# rc1180.net
KiCad netlist of a schematic drawn in EAGLE
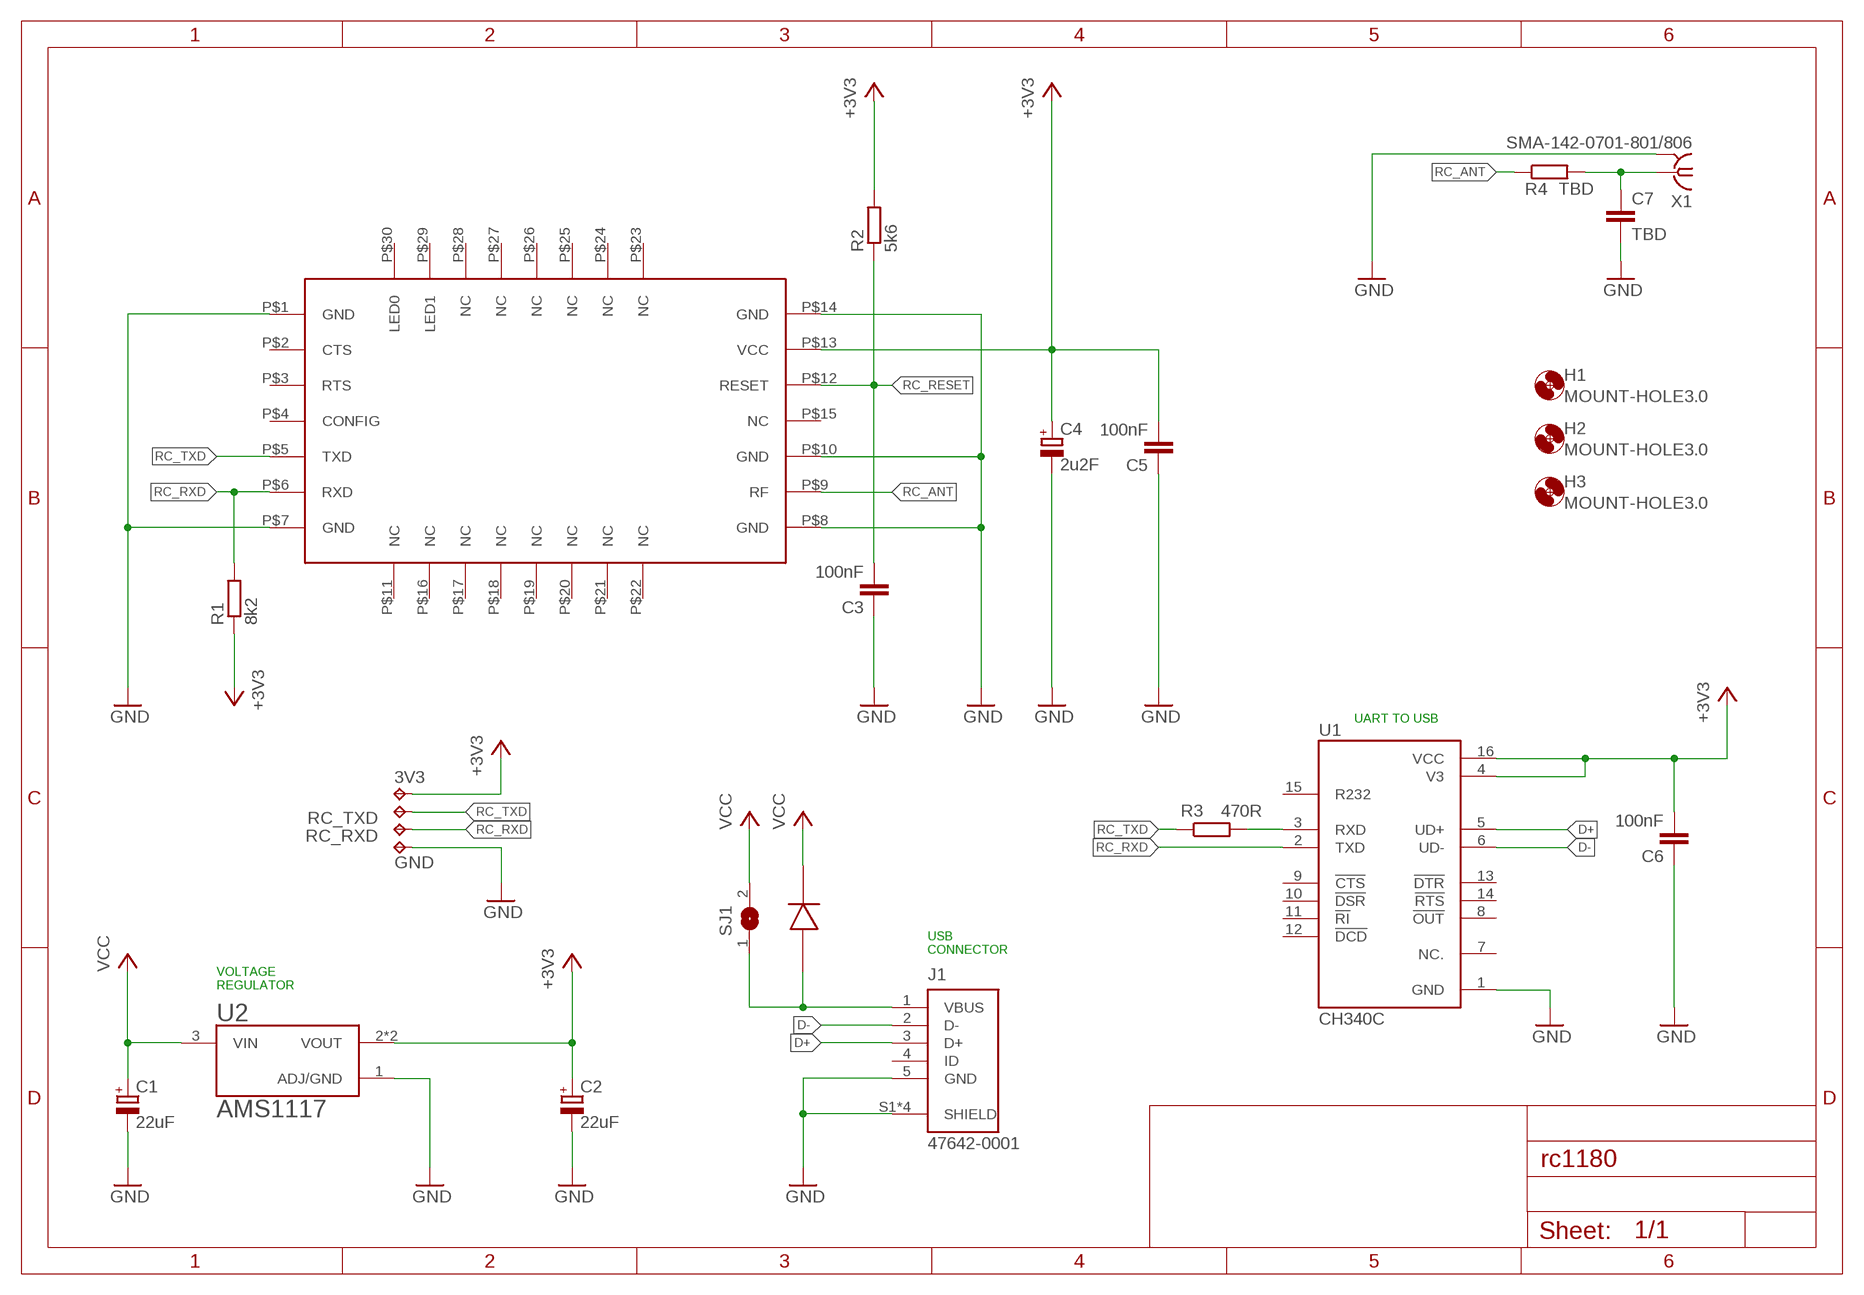
[diagram p0: schematic, sheet 1]

(export (version "E")
  (design (tool "Eeschema 10.0.6"))
  (components
    (comp (ref "3V3")
      (value "TPB1,27")
      (footprint "eagle-import:B1,27")
      (libsource (lib "eagle-import") (part "TPB1,27"))
    )
    (comp (ref "C1")
      (value "22uF")
      (footprint "eagle-import:C_6032-28R")
      (libsource (lib "eagle-import") (part "CPOL-EUC/6032-28R"))
    )
    (comp (ref "C2")
      (value "22uF")
      (footprint "eagle-import:C_6032-28R")
      (libsource (lib "eagle-import") (part "CPOL-EUC/6032-28R"))
    )
    (comp (ref "C3")
      (value "100nF")
      (footprint "eagle-import:C0805K")
      (libsource (lib "eagle-import") (part "C-EUC0805K"))
    )
    (comp (ref "C4")
      (value "2u2F")
      (footprint "eagle-import:A_3216-18W")
      (libsource (lib "eagle-import") (part "CPOL-EUA/3216-18W"))
    )
    (comp (ref "C5")
      (value "100nF")
      (footprint "eagle-import:C0805K")
      (libsource (lib "eagle-import") (part "C-EUC0805K"))
    )
    (comp (ref "C6")
      (value "100nF")
      (footprint "eagle-import:C0805K")
      (libsource (lib "eagle-import") (part "C-EUC0805K"))
    )
    (comp (ref "C7")
      (value "TBD")
      (footprint "eagle-import:C0603")
      (libsource (lib "eagle-import") (part "C-EUC0603"))
    )
    (comp (ref "GND")
      (value "TPB1,27")
      (footprint "eagle-import:B1,27")
      (libsource (lib "eagle-import") (part "TPB1,27"))
    )
    (comp (ref "H1")
      (value "MOUNT-HOLE3.0")
      (footprint "eagle-import:3,0")
      (libsource (lib "eagle-import") (part "MOUNT-HOLE3.0"))
    )
    (comp (ref "H2")
      (value "MOUNT-HOLE3.0")
      (footprint "eagle-import:3,0")
      (libsource (lib "eagle-import") (part "MOUNT-HOLE3.0"))
    )
    (comp (ref "H3")
      (value "MOUNT-HOLE3.0")
      (footprint "eagle-import:3,0")
      (libsource (lib "eagle-import") (part "MOUNT-HOLE3.0"))
    )
    (comp (ref "J1")
      (value "47642-0001")
      (footprint "eagle-import:MOLEX_47642-0001")
      (fields (field (name "MF") "Molex"))
      (libsource (lib "eagle-import") (part "47642-0001"))
    )
    (comp (ref "R1")
      (value "8k2")
      (footprint "eagle-import:R0805")
      (libsource (lib "eagle-import") (part "R-EU_R0805"))
    )
    (comp (ref "R2")
      (value "5k6")
      (footprint "eagle-import:R0805")
      (libsource (lib "eagle-import") (part "R-EU_R0805"))
    )
    (comp (ref "R3")
      (value "470R")
      (footprint "eagle-import:R0805")
      (libsource (lib "eagle-import") (part "R-EU_R0805"))
    )
    (comp (ref "R4")
      (value "TBD")
      (footprint "eagle-import:R0603")
      (libsource (lib "eagle-import") (part "R-EU_R0603"))
    )
    (comp (ref "RC_RXD")
      (value "TPB1,27")
      (footprint "eagle-import:B1,27")
      (libsource (lib "eagle-import") (part "TPB1,27"))
    )
    (comp (ref "RC_TXD")
      (value "TPB1,27")
      (footprint "eagle-import:B1,27")
      (libsource (lib "eagle-import") (part "TPB1,27"))
    )
    (comp (ref "SJ1") (value "SJ") (footprint "eagle-import:SJ") (libsource (lib "eagle-import") (part "SJ")))
    (comp (ref "U$1")
      (value "RC1180-MBUS3")
      (footprint "eagle-import:RC1180-MBUS3")
      (libsource (lib "eagle-import") (part "RC1180-MBUS3"))
    )
    (comp (ref "U$2")
      (value "MBR0540")
      (footprint "eagle-import:SOD123")
      (libsource (lib "eagle-import") (part "MBR0540"))
    )
    (comp (ref "U1")
      (value "CH340C")
      (footprint "eagle-import:SOIC127P600X180-16N")
      (fields (field (name "MANUFACTURER") "WCH"))
      (libsource (lib "eagle-import") (part "CH340C"))
    )
    (comp (ref "U2")
      (value "AMS1117")
      (footprint "eagle-import:SOT229P700X180-4N")
      (fields (field (name "MANUFACTURER") "AMS"))
      (libsource (lib "eagle-import") (part "AMS1117"))
    )
    (comp (ref "X1")
      (value "SMA-142-0701-801/806")
      (footprint "eagle-import:J502-ND-142-0701-801_806")
      (fields (field (name "MF") "JOHNSON COMPONENTS") (field (name "MPN") "142-0701-801"))
      (libsource (lib "eagle-import") (part "SMA-142-0701-801/806"))
    )
  )
  (nets
    (net (code "1") (name "+3V3") (class "Default")
      (node (ref "3V3") (pin "TP") (pinfunction "TP_TP") (pintype "input"))
      (node (ref "C2") (pin "+") (pinfunction "+_+") (pintype "passive"))
      (node (ref "C4") (pin "+") (pinfunction "+_+") (pintype "passive"))
      (node (ref "C5") (pin "2") (pinfunction "2_2") (pintype "passive"))
      (node (ref "C6") (pin "2") (pinfunction "2_2") (pintype "passive"))
      (node (ref "R1") (pin "1") (pinfunction "1_1") (pintype "passive"))
      (node (ref "R2") (pin "2") (pinfunction "2_2") (pintype "passive"))
      (node (ref "U$1") (pin "P$13") (pinfunction "VCC_P$13") (pintype "bidirectional"))
      (node (ref "U1") (pin "16") (pinfunction "VCC_16") (pintype "power_in"))
      (node (ref "U1") (pin "4") (pinfunction "V3_4") (pintype "power_in"))
      (node (ref "U2") (pin "2") (pinfunction "VOUT_2") (pintype "output"))
      (node (ref "U2") (pin "4") (pinfunction "VOUT_4") (pintype "output"))
    )
    (net (code "2") (name "D+") (class "Default")
      (node (ref "J1") (pin "3") (pinfunction "D+_3") (pintype "bidirectional"))
      (node (ref "U1") (pin "5") (pinfunction "UD+_5") (pintype "bidirectional"))
    )
    (net (code "3") (name "D-") (class "Default")
      (node (ref "J1") (pin "2") (pinfunction "D-_2") (pintype "bidirectional"))
      (node (ref "U1") (pin "6") (pinfunction "UD-_6") (pintype "bidirectional"))
    )
    (net (code "4") (name "GND") (class "Default")
      (node (ref "C1") (pin "-") (pinfunction "-_-") (pintype "passive"))
      (node (ref "C2") (pin "-") (pinfunction "-_-") (pintype "passive"))
      (node (ref "C3") (pin "1") (pinfunction "1_1") (pintype "passive"))
      (node (ref "C4") (pin "-") (pinfunction "-_-") (pintype "passive"))
      (node (ref "C5") (pin "1") (pinfunction "1_1") (pintype "passive"))
      (node (ref "C6") (pin "1") (pinfunction "1_1") (pintype "passive"))
      (node (ref "C7") (pin "2") (pinfunction "2_2") (pintype "passive"))
      (node (ref "GND") (pin "TP") (pinfunction "TP_TP") (pintype "input"))
      (node (ref "J1") (pin "5") (pinfunction "GND_5") (pintype "power_in"))
      (node (ref "J1") (pin "S1") (pinfunction "SHIELD_S1") (pintype "power_in"))
      (node (ref "J1") (pin "S2") (pinfunction "SHIELD_S2") (pintype "power_in"))
      (node (ref "J1") (pin "S3") (pinfunction "SHIELD_S3") (pintype "power_in"))
      (node (ref "J1") (pin "S4") (pinfunction "SHIELD_S4") (pintype "power_in"))
      (node (ref "U$1") (pin "P$1") (pinfunction "GND_P$1") (pintype "power_in"))
      (node (ref "U$1") (pin "P$10") (pinfunction "GND_P$10") (pintype "power_in"))
      (node (ref "U$1") (pin "P$14") (pinfunction "GND_P$14") (pintype "power_in"))
      (node (ref "U$1") (pin "P$7") (pinfunction "GND_P$7") (pintype "power_in"))
      (node (ref "U$1") (pin "P$8") (pinfunction "GND_P$8") (pintype "power_in"))
      (node (ref "U1") (pin "1") (pinfunction "GND_1") (pintype "power_in"))
      (node (ref "U2") (pin "1") (pinfunction "ADJ/GND_1") (pintype "power_in"))
      (node (ref "X1") (pin "G@1") (pinfunction "2_G@1") (pintype "passive"))
      (node (ref "X1") (pin "G@2") (pinfunction "2_G@2") (pintype "passive"))
      (node (ref "X1") (pin "G@3") (pinfunction "2_G@3") (pintype "passive"))
      (node (ref "X1") (pin "G@4") (pinfunction "2_G@4") (pintype "passive"))
    )
    (net (code "5") (name "Net-(C7-Pad1)") (class "Default")
      (node (ref "C7") (pin "1") (pinfunction "1_1") (pintype "passive"))
      (node (ref "R4") (pin "2") (pinfunction "2_2") (pintype "passive"))
      (node (ref "X1") (pin "1") (pinfunction "1_1") (pintype "passive"))
    )
    (net (code "6") (name "Net-(J1-VBUS)") (class "Default")
      (node (ref "J1") (pin "1") (pinfunction "VBUS_1") (pintype "power_in"))
      (node (ref "SJ1") (pin "1") (pinfunction "1_1") (pintype "passive"))
      (node (ref "U$2") (pin "A") (pinfunction "A_A") (pintype "bidirectional"))
    )
    (net (code "7") (name "Net-(U1-RXD)") (class "Default")
      (node (ref "R3") (pin "2") (pinfunction "2_2") (pintype "passive"))
      (node (ref "U1") (pin "3") (pinfunction "RXD_3") (pintype "input"))
    )
    (net (code "8") (name "RC_ANT") (class "Default")
      (node (ref "R4") (pin "1") (pinfunction "1_1") (pintype "passive"))
      (node (ref "U$1") (pin "P$9") (pinfunction "RF_P$9") (pintype "bidirectional"))
    )
    (net (code "9") (name "RC_RESET") (class "Default")
      (node (ref "C3") (pin "2") (pinfunction "2_2") (pintype "passive"))
      (node (ref "R2") (pin "1") (pinfunction "1_1") (pintype "passive"))
      (node (ref "U$1") (pin "P$12") (pinfunction "RESET_P$12") (pintype "power_in"))
    )
    (net (code "10") (name "RC_RXD") (class "Default")
      (node (ref "R1") (pin "2") (pinfunction "2_2") (pintype "passive"))
      (node (ref "RC_RXD") (pin "TP") (pinfunction "TP_TP") (pintype "input"))
      (node (ref "U$1") (pin "P$6") (pinfunction "RXD_P$6") (pintype "bidirectional"))
      (node (ref "U1") (pin "2") (pinfunction "TXD_2") (pintype "output"))
    )
    (net (code "11") (name "RC_TXD") (class "Default")
      (node (ref "R3") (pin "1") (pinfunction "1_1") (pintype "passive"))
      (node (ref "RC_TXD") (pin "TP") (pinfunction "TP_TP") (pintype "input"))
      (node (ref "U$1") (pin "P$5") (pinfunction "TXD_P$5") (pintype "bidirectional"))
    )
    (net (code "12") (name "VCC") (class "Default")
      (node (ref "C1") (pin "+") (pinfunction "+_+") (pintype "passive"))
      (node (ref "SJ1") (pin "2") (pinfunction "2_2") (pintype "passive"))
      (node (ref "U$2") (pin "C") (pinfunction "K_C") (pintype "bidirectional"))
      (node (ref "U2") (pin "3") (pinfunction "VIN_3") (pintype "input"))
    )
    (net (code "13") (name "unconnected-(J1-ID-Pad4)") (class "Default")
      (node (ref "J1") (pin "4") (pinfunction "ID_4") (pintype "bidirectional"))
    )
    (net (code "14") (name "unconnected-(U$1-CONFIG-PadP$4)") (class "Default")
      (node (ref "U$1") (pin "P$4") (pinfunction "CONFIG_P$4") (pintype "bidirectional"))
    )
    (net (code "15") (name "unconnected-(U$1-CTS-PadP$2)") (class "Default")
      (node (ref "U$1") (pin "P$2") (pinfunction "CTS_P$2") (pintype "bidirectional"))
    )
    (net (code "16") (name "unconnected-(U$1-LED0-PadP$30)") (class "Default")
      (node (ref "U$1") (pin "P$30") (pinfunction "LED0_P$30") (pintype "bidirectional"))
    )
    (net (code "17") (name "unconnected-(U$1-LED1-PadP$29)") (class "Default")
      (node (ref "U$1") (pin "P$29") (pinfunction "LED1_P$29") (pintype "bidirectional"))
    )
    (net (code "18") (name "unconnected-(U$1-NC-PadP$11)") (class "Default")
      (node (ref "U$1") (pin "P$11") (pinfunction "NC_P$11") (pintype "bidirectional"))
    )
    (net (code "19") (name "unconnected-(U$1-NC-PadP$15)") (class "Default")
      (node (ref "U$1") (pin "P$15") (pinfunction "NC_P$15") (pintype "bidirectional"))
    )
    (net (code "20") (name "unconnected-(U$1-NC-PadP$16)") (class "Default")
      (node (ref "U$1") (pin "P$16") (pinfunction "NC_P$16") (pintype "bidirectional"))
    )
    (net (code "21") (name "unconnected-(U$1-NC-PadP$17)") (class "Default")
      (node (ref "U$1") (pin "P$17") (pinfunction "NC_P$17") (pintype "bidirectional"))
    )
    (net (code "22") (name "unconnected-(U$1-NC-PadP$18)") (class "Default")
      (node (ref "U$1") (pin "P$18") (pinfunction "NC_P$18") (pintype "bidirectional"))
    )
    (net (code "23") (name "unconnected-(U$1-NC-PadP$19)") (class "Default")
      (node (ref "U$1") (pin "P$19") (pinfunction "NC_P$19") (pintype "bidirectional"))
    )
    (net (code "24") (name "unconnected-(U$1-NC-PadP$20)") (class "Default")
      (node (ref "U$1") (pin "P$20") (pinfunction "NC_P$20") (pintype "bidirectional"))
    )
    (net (code "25") (name "unconnected-(U$1-NC-PadP$21)") (class "Default")
      (node (ref "U$1") (pin "P$21") (pinfunction "NC_P$21") (pintype "bidirectional"))
    )
    (net (code "26") (name "unconnected-(U$1-NC-PadP$22)") (class "Default")
      (node (ref "U$1") (pin "P$22") (pinfunction "NC_P$22") (pintype "bidirectional"))
    )
    (net (code "27") (name "unconnected-(U$1-NC-PadP$23)") (class "Default")
      (node (ref "U$1") (pin "P$23") (pinfunction "NC_P$23") (pintype "bidirectional"))
    )
    (net (code "28") (name "unconnected-(U$1-NC-PadP$24)") (class "Default")
      (node (ref "U$1") (pin "P$24") (pinfunction "NC_P$24") (pintype "bidirectional"))
    )
    (net (code "29") (name "unconnected-(U$1-NC-PadP$25)") (class "Default")
      (node (ref "U$1") (pin "P$25") (pinfunction "NC_P$25") (pintype "bidirectional"))
    )
    (net (code "30") (name "unconnected-(U$1-NC-PadP$26)") (class "Default")
      (node (ref "U$1") (pin "P$26") (pinfunction "NC_P$26") (pintype "bidirectional"))
    )
    (net (code "31") (name "unconnected-(U$1-NC-PadP$27)") (class "Default")
      (node (ref "U$1") (pin "P$27") (pinfunction "NC_P$27") (pintype "bidirectional"))
    )
    (net (code "32") (name "unconnected-(U$1-NC-PadP$28)") (class "Default")
      (node (ref "U$1") (pin "P$28") (pinfunction "NC_P$28") (pintype "bidirectional"))
    )
    (net (code "33") (name "unconnected-(U$1-RTS-PadP$3)") (class "Default")
      (node (ref "U$1") (pin "P$3") (pinfunction "RTS_P$3") (pintype "bidirectional"))
    )
    (net (code "34") (name "unconnected-(U1-NC.-Pad7)") (class "Default")
      (node (ref "U1") (pin "7") (pinfunction "NC._7") (pintype "no_connect"))
    )
    (net (code "35") (name "unconnected-(U1-R232-Pad15)") (class "Default")
      (node (ref "U1") (pin "15") (pinfunction "R232_15") (pintype "input"))
    )
    (net (code "36") (name "unconnected-(U1-~{CTS}-Pad9)") (class "Default")
      (node (ref "U1") (pin "9") (pinfunction "~{CTS}_9") (pintype "input"))
    )
    (net (code "37") (name "unconnected-(U1-~{DCD}-Pad12)") (class "Default")
      (node (ref "U1") (pin "12") (pinfunction "~{DCD}_12") (pintype "input"))
    )
    (net (code "38") (name "unconnected-(U1-~{DSR}-Pad10)") (class "Default")
      (node (ref "U1") (pin "10") (pinfunction "~{DSR}_10") (pintype "input"))
    )
    (net (code "39") (name "unconnected-(U1-~{DTR}-Pad13)") (class "Default")
      (node (ref "U1") (pin "13") (pinfunction "~{DTR}_13") (pintype "output"))
    )
    (net (code "40") (name "unconnected-(U1-~{OUT}-Pad8)") (class "Default")
      (node (ref "U1") (pin "8") (pinfunction "~{OUT}_8") (pintype "output"))
    )
    (net (code "41") (name "unconnected-(U1-~{RI}-Pad11)") (class "Default")
      (node (ref "U1") (pin "11") (pinfunction "~{RI}_11") (pintype "input"))
    )
    (net (code "42") (name "unconnected-(U1-~{RTS}-Pad14)") (class "Default")
      (node (ref "U1") (pin "14") (pinfunction "~{RTS}_14") (pintype "output"))
    )
  )
)
